# miniMagSwitch.net
KiCad netlist of a schematic drawn in EasyEDA Pro
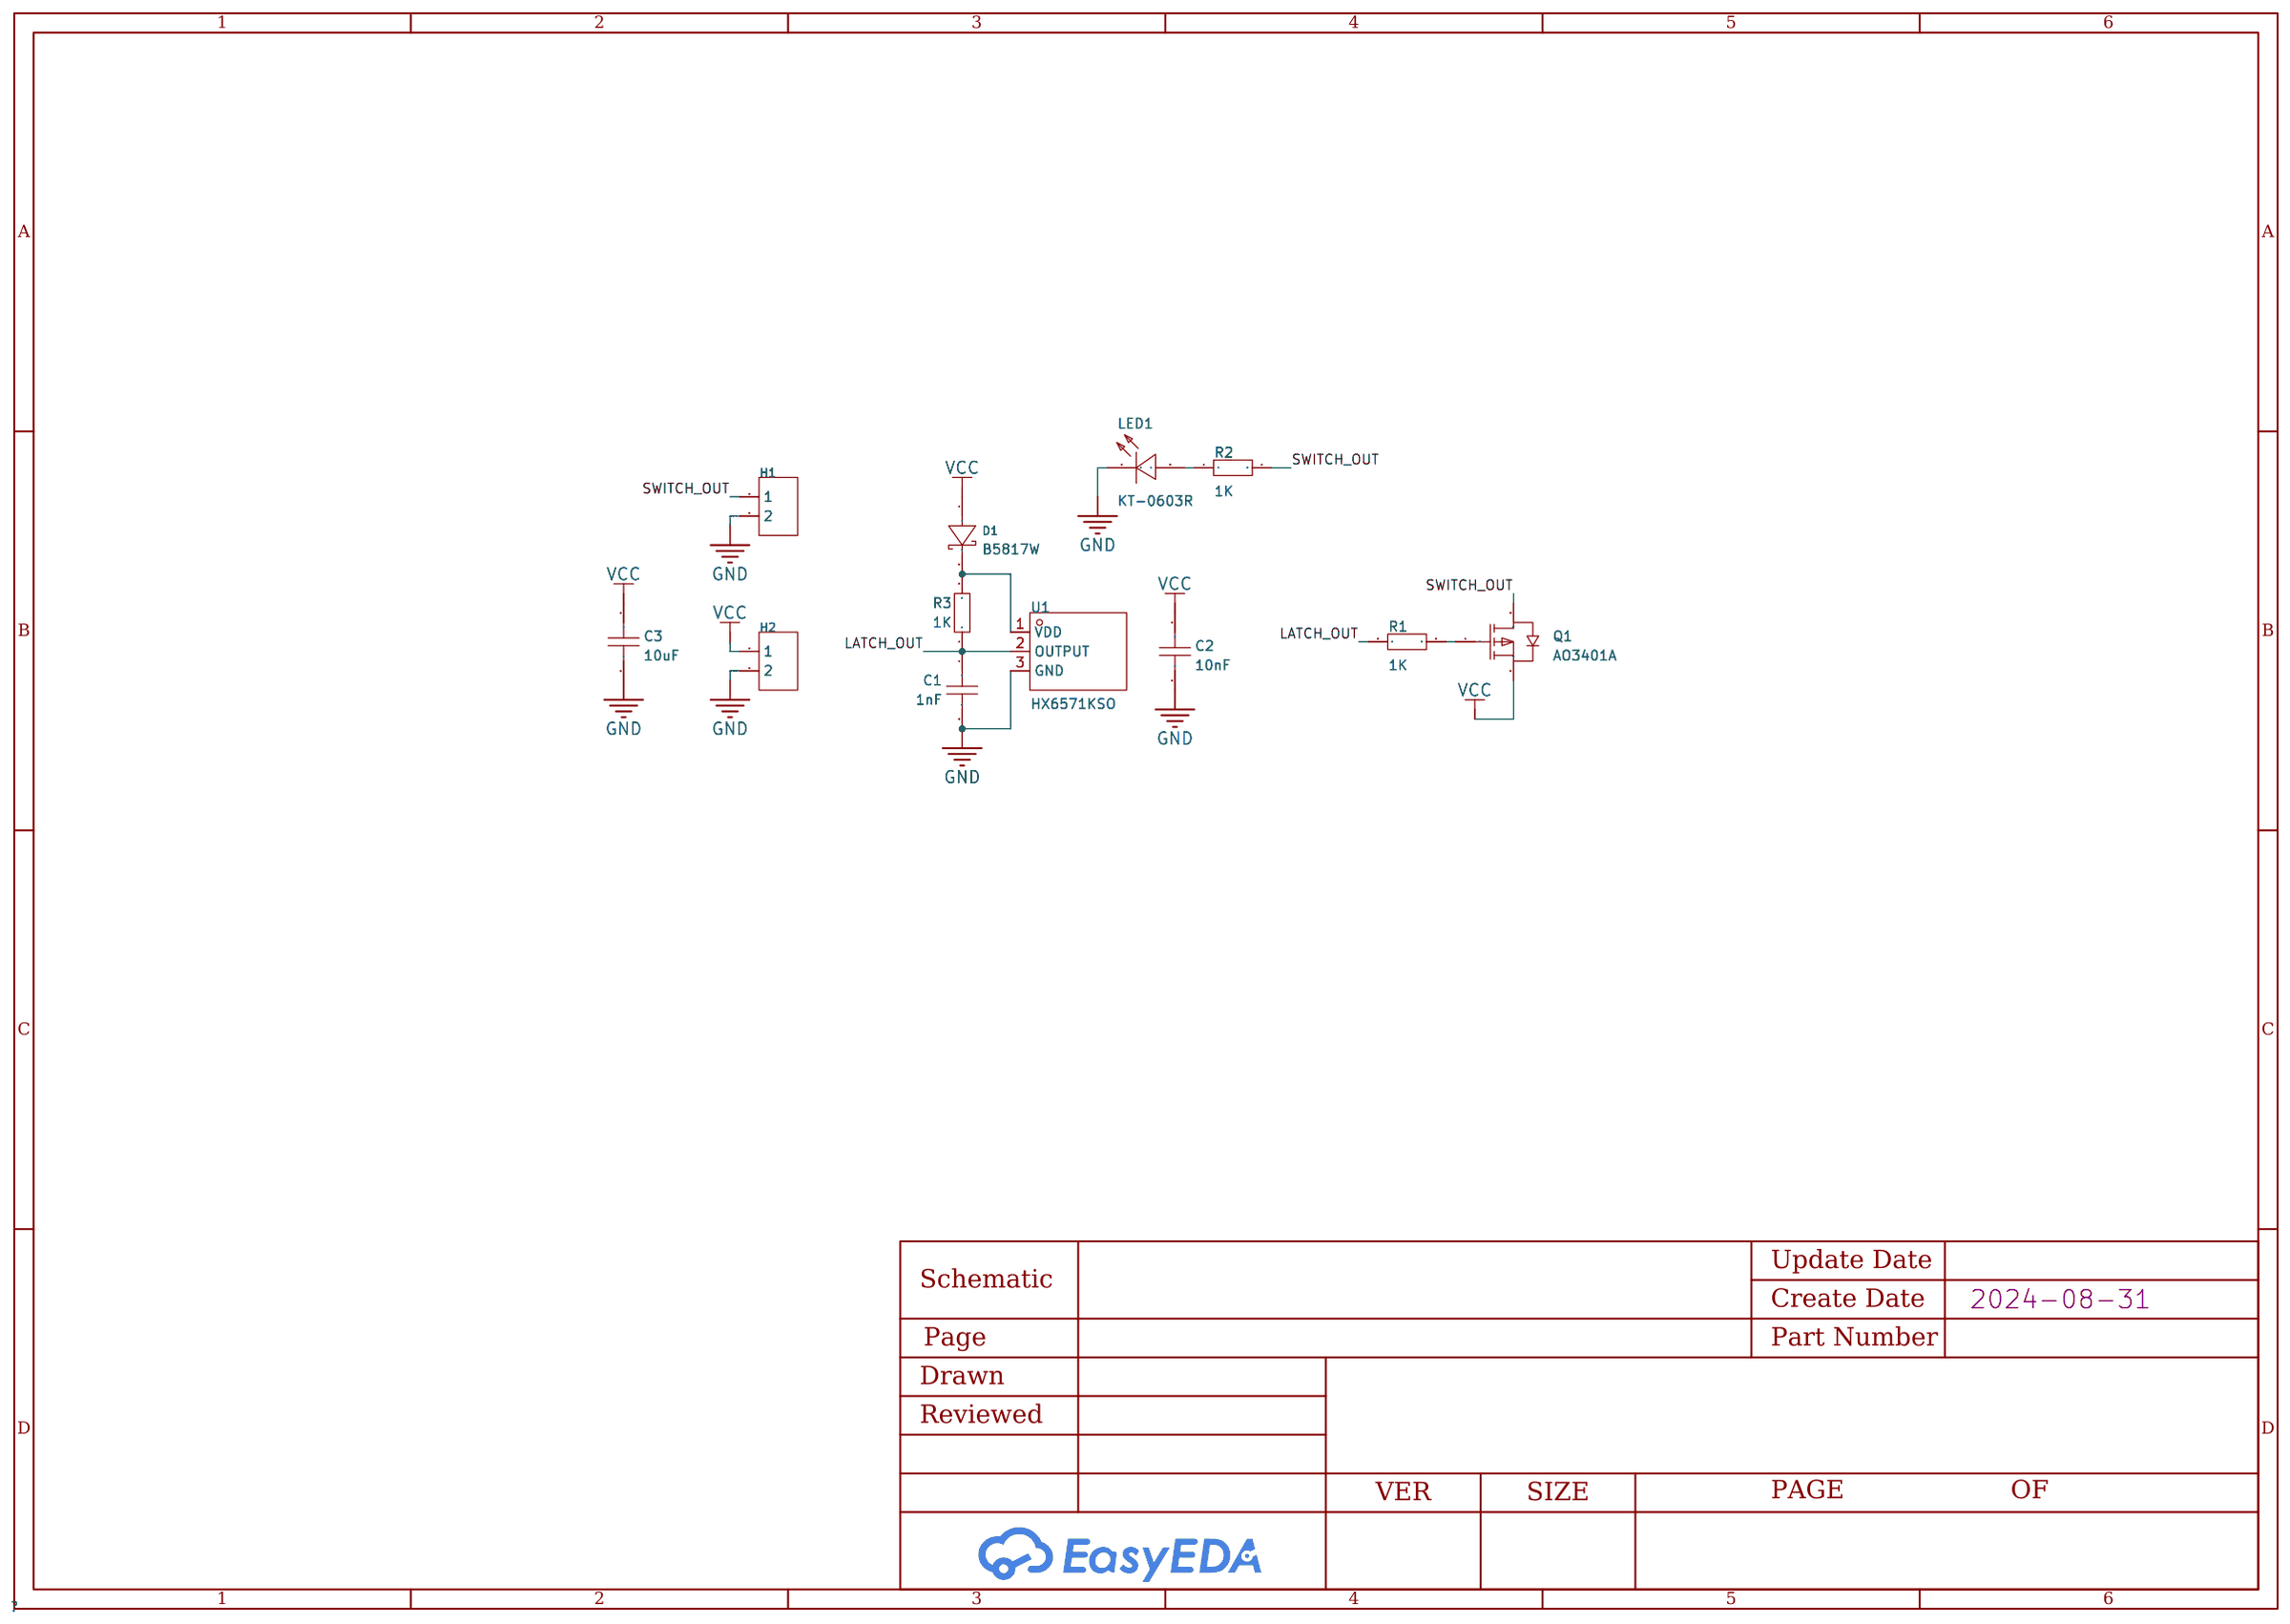
[diagram p0: schematic sheet]

(export (version "E")
  (design (tool "Eeschema 10.0.6"))
  (components
    (comp (ref "C1") (value "1nF") (footprint "easyedapro:C0603") (libsource (lib "easyedapro") (part "CAP")))
    (comp (ref "C2")
      (value "10nF")
      (footprint "easyedapro:C0603")
      (libsource (lib "easyedapro") (part "CAP"))
    )
    (comp (ref "C3")
      (value "10uF")
      (footprint "easyedapro:C0603")
      (libsource (lib "easyedapro") (part "CAP"))
    )
    (comp (ref "D1")
      (value "B5817W")
      (footprint "easyedapro:SOD-123_L2.7-W1.6-LS3.7-FD")
      (fields (field (name "Manufacturer") "宏迦橙"))
      (libsource (lib "easyedapro") (part "B5817W_C7420328"))
    )
    (comp (ref "H1")
      (value "~")
      (footprint "easyedapro:HDR-TH_2P-P2.54-V-F")
      (libsource (lib "easyedapro") (part "Header-Female-2.54_1x2"))
    )
    (comp (ref "H2")
      (value "~")
      (footprint "easyedapro:HDR-TH_2P-P2.54-V-F")
      (libsource (lib "easyedapro") (part "Header-Female-2.54_1x2"))
    )
    (comp (ref "LED1")
      (value "KT-0603R")
      (footprint "easyedapro:LED0603-RD")
      (fields (field (name "Manufacturer") "KENTO"))
      (libsource (lib "easyedapro") (part "KT-0603R"))
    )
    (comp (ref "Q1")
      (value "AO3401A")
      (footprint "easyedapro:SOT-23_L2.9-W1.3-P1.90-LS2.4-BR")
      (fields (field (name "Manufacturer") "AOS"))
      (libsource (lib "easyedapro") (part "AO3401A"))
    )
    (comp (ref "R1") (value "1K") (footprint "easyedapro:R0603") (libsource (lib "easyedapro") (part "Res")))
    (comp (ref "R2") (value "1K") (footprint "easyedapro:R0603") (libsource (lib "easyedapro") (part "Res")))
    (comp (ref "R3") (value "1K") (footprint "easyedapro:R0603") (libsource (lib "easyedapro") (part "Res")))
    (comp (ref "U1")
      (value "HX6571KSO")
      (footprint "easyedapro:SOT-23-3_L2.9-W1.5-P1.90-LS2.8-BR-1")
      (fields (field (name "Manufacturer") "HUAXIN(华芯)"))
      (libsource (lib "easyedapro") (part "HX6571KSO"))
    )
  )
  (nets
    (net (code "1") (name "/LATCH_OUT") (class "Default")
      (node (ref "C1") (pin "1") (pinfunction "1_1") (pintype "input"))
      (node (ref "R1") (pin "2") (pinfunction "2_2") (pintype "input"))
      (node (ref "R3") (pin "1") (pinfunction "1_1") (pintype "input"))
      (node (ref "U1") (pin "2") (pinfunction "OUTPUT_2") (pintype "unspecified"))
    )
    (net (code "2") (name "/SWITCH_OUT") (class "Default")
      (node (ref "H1") (pin "1") (pinfunction "1_1") (pintype "input"))
      (node (ref "Q1") (pin "3") (pinfunction "D_3") (pintype "unspecified"))
      (node (ref "R2") (pin "2") (pinfunction "2_2") (pintype "input"))
    )
    (net (code "3") (name "GND") (class "Default")
      (node (ref "C1") (pin "2") (pinfunction "2_2") (pintype "input"))
      (node (ref "C2") (pin "2") (pinfunction "2_2") (pintype "input"))
      (node (ref "C3") (pin "2") (pinfunction "2_2") (pintype "input"))
      (node (ref "H1") (pin "2") (pinfunction "2_2") (pintype "input"))
      (node (ref "H2") (pin "2") (pinfunction "2_2") (pintype "input"))
      (node (ref "LED1") (pin "1") (pinfunction "K_1") (pintype "input"))
      (node (ref "U1") (pin "3") (pinfunction "GND_3") (pintype "unspecified"))
    )
    (net (code "4") (name "Net-(D1-K)") (class "Default")
      (node (ref "D1") (pin "2") (pinfunction "K_2") (pintype "input"))
      (node (ref "R3") (pin "2") (pinfunction "2_2") (pintype "input"))
      (node (ref "U1") (pin "1") (pinfunction "VDD_1") (pintype "unspecified"))
    )
    (net (code "5") (name "Net-(LED1-A)") (class "Default")
      (node (ref "LED1") (pin "2") (pinfunction "A_2") (pintype "input"))
      (node (ref "R2") (pin "1") (pinfunction "1_1") (pintype "input"))
    )
    (net (code "6") (name "Net-(Q1-G)") (class "Default")
      (node (ref "Q1") (pin "1") (pinfunction "G_1") (pintype "unspecified"))
      (node (ref "R1") (pin "1") (pinfunction "1_1") (pintype "input"))
    )
    (net (code "7") (name "VCC") (class "Default")
      (node (ref "C2") (pin "1") (pinfunction "1_1") (pintype "input"))
      (node (ref "C3") (pin "1") (pinfunction "1_1") (pintype "input"))
      (node (ref "D1") (pin "1") (pinfunction "A_1") (pintype "input"))
      (node (ref "H2") (pin "1") (pinfunction "1_1") (pintype "input"))
      (node (ref "Q1") (pin "2") (pinfunction "S_2") (pintype "unspecified"))
    )
  )
)
